# encoder.net
KiCad netlist of a schematic drawn in Altium Designer
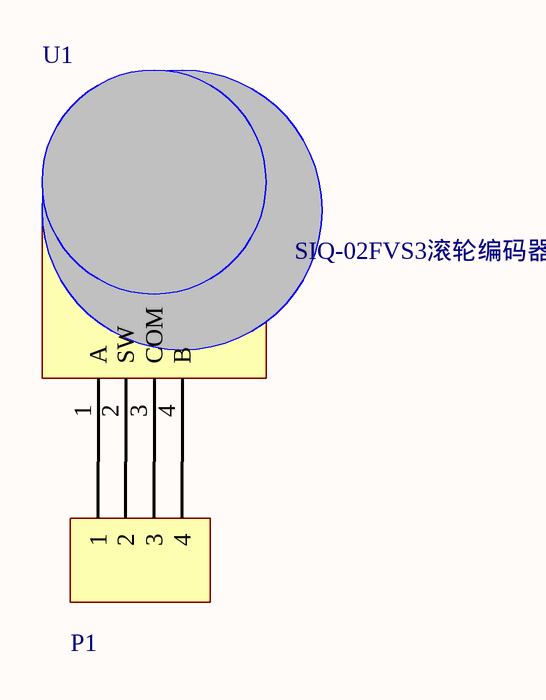
[diagram p0: encoder.SchDoc]

(export (version "E")
  (design (tool "Eeschema 10.0.6"))
  (components
    (comp (ref "P1")
      (value "~")
      (footprint "MX1.25-4P 卧")
      (description "Header, 4-Pin")
      (fields (field (name "PUBLISHER") "Altium Limited"))
      (libsource (lib "Miscellaneous Connectors") (part "Header 4"))
    )
    (comp (ref "U1")
      (value "SIQ-02FVS3滚轮编码器")
      (footprint "美上美SIQ-02FVS3滚轮编码器")
      (libsource (lib "zhjrm") (part "SIQ-02FVS3滚轮编码器"))
    )
  )
  (nets
    (net (code "1") (name "Net-(U1-A)") (class "Default")
      (node (ref "P1") (pin "1") (pinfunction "1_1") (pintype "passive"))
      (node (ref "U1") (pin "1") (pinfunction "A_1") (pintype "passive"))
    )
    (net (code "2") (name "Net-(U1-B)") (class "Default")
      (node (ref "P1") (pin "4") (pinfunction "4_4") (pintype "passive"))
      (node (ref "U1") (pin "4") (pinfunction "B_4") (pintype "passive"))
    )
    (net (code "3") (name "Net-(U1-COM)") (class "Default")
      (node (ref "P1") (pin "3") (pinfunction "3_3") (pintype "passive"))
      (node (ref "U1") (pin "3") (pinfunction "COM_3") (pintype "passive"))
    )
    (net (code "4") (name "Net-(U1-SW)") (class "Default")
      (node (ref "P1") (pin "2") (pinfunction "2_2") (pintype "passive"))
      (node (ref "U1") (pin "2") (pinfunction "SW_2") (pintype "passive"))
    )
  )
)
